# PowerSupply.net
KiCad netlist of a schematic drawn in Altium Designer
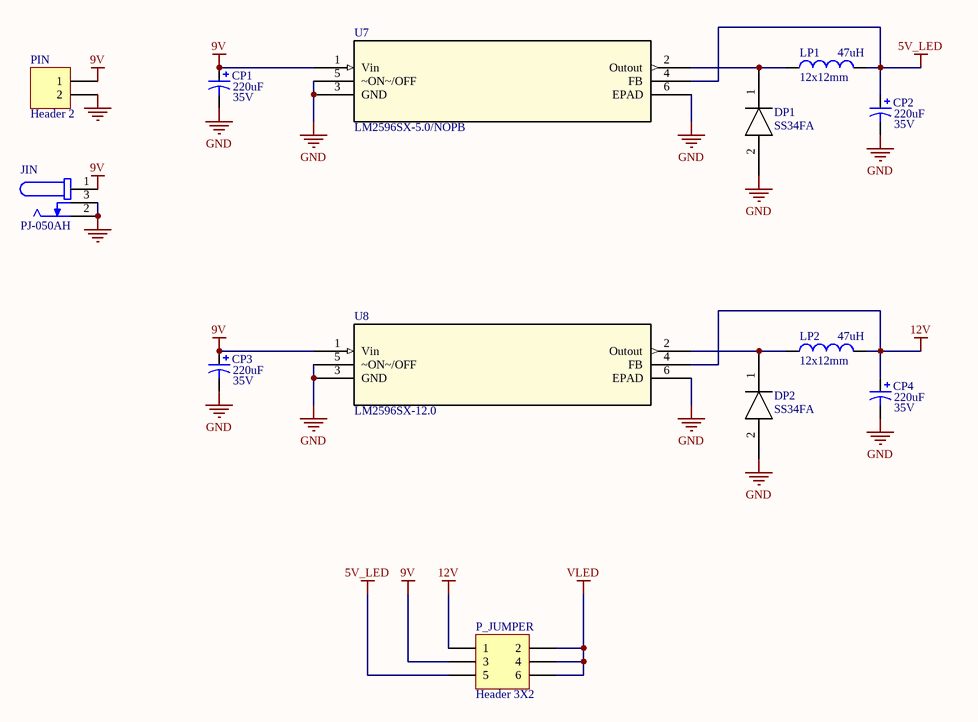
[diagram p0: PowerSupply.SchDoc]

(export (version "E")
  (design (tool "Eeschema 10.0.6"))
  (components
    (comp (ref "CP1")
      (value "220uF")
      (footprint "Cap10x10")
      (description "CAP ALUM 220UF 20% 35V SMD")
      (fields
        (field (name "TOLERANCE") "20%")
        (field (name "VOLTAGE") "35V")
        (field (name "Comment") "Cap Pol")
      )
      (libsource (lib "Miscellaneous Devices") (part "Cap Pol1"))
    )
    (comp (ref "CP2")
      (value "220uF")
      (footprint "Cap10x10")
      (description "CAP ALUM 220UF 20% 35V SMD")
      (fields
        (field (name "TOLERANCE") "20%")
        (field (name "VOLTAGE") "35V")
        (field (name "Comment") "Cap Pol")
      )
      (libsource (lib "Miscellaneous Devices") (part "Cap Pol1"))
    )
    (comp (ref "CP3")
      (value "220uF")
      (footprint "Cap10x10")
      (description "CAP ALUM 220UF 20% 35V SMD")
      (fields
        (field (name "TOLERANCE") "20%")
        (field (name "VOLTAGE") "35V")
        (field (name "Comment") "Cap Pol")
      )
      (libsource (lib "Miscellaneous Devices") (part "Cap Pol1"))
    )
    (comp (ref "CP4")
      (value "220uF")
      (footprint "Cap10x10")
      (description "CAP ALUM 220UF 20% 35V SMD")
      (fields
        (field (name "TOLERANCE") "20%")
        (field (name "VOLTAGE") "35V")
        (field (name "Comment") "Cap Pol")
      )
      (libsource (lib "Miscellaneous Devices") (part "Cap Pol1"))
    )
    (comp (ref "DP1")
      (value "SS34FA")
      (footprint "SOD_34FA_ONS")
      (description "DIODE SCHOTTKY 40V 3A SOD123FA")
      (fields (field (name "COPYRIGHT") "Copyright (C) 2018 Accelerated Designs. All rights reserved"))
      (libsource (lib "Symbols") (part "SS34FA"))
    )
    (comp (ref "DP2")
      (value "SS34FA")
      (footprint "SOD_34FA_ONS")
      (description "DIODE SCHOTTKY 40V 3A SOD123FA")
      (fields (field (name "COPYRIGHT") "Copyright (C) 2018 Accelerated Designs. All rights reserved"))
      (libsource (lib "Symbols") (part "SS34FA"))
    )
    (comp (ref "JIN")
      (value "PJ-050AH")
      (footprint "CUI_PJ-050AH")
      (description "2.0 x 6.0 mm, 5.0 A, Horizontal, Through Hole, Pick-n-Place Top, Dc Power Jack Connector")
      (fields (field (name "MF") "CUI Devices"))
      (libsource (lib "Schlib") (part "PJ-050AH"))
    )
    (comp (ref "LP1")
      (value "12x12mm")
      (footprint "12x12mmInductor")
      (description "FIXED IND 47UH 3.8A 60 MOHM SMD")
      (fields (field (name "ALTIUM_VALUE") "47uH") (field (name "TOLERANCE") "20%"))
      (libsource (lib "Miscellaneous Devices") (part "Inductor"))
    )
    (comp (ref "LP2")
      (value "12x12mm")
      (footprint "12x12mmInductor")
      (description "FIXED IND 47UH 3.8A 60 MOHM SMD")
      (fields (field (name "ALTIUM_VALUE") "47uH") (field (name "TOLERANCE") "20%"))
      (libsource (lib "Miscellaneous Devices") (part "Inductor"))
    )
    (comp (ref "PIN")
      (value "Header 2")
      (footprint "5.08mmScrew")
      (description "TERMINAL BLOCK, SCREW TYPE, 5.08")
      (fields (field (name "PUBLISHER") "Altium Limited"))
      (libsource (lib "Miscellaneous Connectors") (part "Header 2"))
    )
    (comp (ref "P_JUMPER")
      (value "Header 3X2")
      (footprint "HDR2X3")
      (description "CONN HEADER VERT 6POS 2.54MM")
      (fields (field (name "PUBLISHER") "Altium Limited"))
      (libsource (lib "Miscellaneous Connectors") (part "Header 3X2"))
    )
    (comp (ref "U7")
      (value "LM2596SX-5.0/NOPB")
      (footprint "TS5B")
      (fields (field (name "COPYRIGHT") "Copyright (C) 2018 Accelerated Designs. All rights reserved"))
      (libsource (lib "Schlib") (part "LM2596SX-5.0/NOP"))
    )
    (comp (ref "U8")
      (value "LM2596SX-12.0")
      (footprint "TS5B")
      (libsource (lib "Schlib") (part "LM2596SX-5.0/NOP"))
    )
  )
  (nets
    (net (code "1") (name "5V_LED") (class "Default")
      (node (ref "CP2") (pin "1") (pinfunction "1_1") (pintype "passive"))
      (node (ref "LP1") (pin "2") (pinfunction "2_2") (pintype "passive"))
      (node (ref "P_JUMPER") (pin "5") (pinfunction "5_5") (pintype "passive"))
      (node (ref "U7") (pin "4") (pinfunction "FB_4") (pintype "passive"))
    )
    (net (code "2") (name "9V") (class "Default")
      (node (ref "CP1") (pin "1") (pinfunction "1_1") (pintype "passive"))
      (node (ref "CP3") (pin "1") (pinfunction "1_1") (pintype "passive"))
      (node (ref "JIN") (pin "1") (pinfunction "1_1") (pintype "passive"))
      (node (ref "PIN") (pin "1") (pinfunction "1_1") (pintype "passive"))
      (node (ref "P_JUMPER") (pin "3") (pinfunction "3_3") (pintype "passive"))
      (node (ref "U7") (pin "1") (pinfunction "Vin_1") (pintype "input"))
      (node (ref "U8") (pin "1") (pinfunction "Vin_1") (pintype "input"))
    )
    (net (code "3") (name "12V") (class "Default")
      (node (ref "CP4") (pin "1") (pinfunction "1_1") (pintype "passive"))
      (node (ref "LP2") (pin "2") (pinfunction "2_2") (pintype "passive"))
      (node (ref "P_JUMPER") (pin "1") (pinfunction "1_1") (pintype "passive"))
      (node (ref "U8") (pin "4") (pinfunction "FB_4") (pintype "passive"))
    )
    (net (code "4") (name "GND") (class "Default")
      (node (ref "CP1") (pin "2") (pinfunction "2_2") (pintype "passive"))
      (node (ref "CP2") (pin "2") (pinfunction "2_2") (pintype "passive"))
      (node (ref "CP3") (pin "2") (pinfunction "2_2") (pintype "passive"))
      (node (ref "CP4") (pin "2") (pinfunction "2_2") (pintype "passive"))
      (node (ref "DP1") (pin "2") (pinfunction "2_2") (pintype "passive"))
      (node (ref "DP2") (pin "2") (pinfunction "2_2") (pintype "passive"))
      (node (ref "JIN") (pin "2") (pinfunction "2_2") (pintype "passive"))
      (node (ref "JIN") (pin "3") (pinfunction "3_3") (pintype "passive"))
      (node (ref "PIN") (pin "2") (pinfunction "2_2") (pintype "passive"))
      (node (ref "U7") (pin "3") (pinfunction "GND_3") (pintype "passive"))
      (node (ref "U7") (pin "5") (pinfunction "~ON~/OFF_5") (pintype "passive"))
      (node (ref "U7") (pin "6") (pinfunction "EPAD_6") (pintype "passive"))
      (node (ref "U8") (pin "3") (pinfunction "GND_3") (pintype "passive"))
      (node (ref "U8") (pin "5") (pinfunction "~ON~/OFF_5") (pintype "passive"))
      (node (ref "U8") (pin "6") (pinfunction "EPAD_6") (pintype "passive"))
    )
    (net (code "5") (name "Net-(U7-Outout)") (class "Default")
      (node (ref "DP1") (pin "1") (pinfunction "1_1") (pintype "passive"))
      (node (ref "LP1") (pin "1") (pinfunction "1_1") (pintype "passive"))
      (node (ref "U7") (pin "2") (pinfunction "Outout_2") (pintype "output"))
    )
    (net (code "6") (name "Net-(U8-Outout)") (class "Default")
      (node (ref "DP2") (pin "1") (pinfunction "1_1") (pintype "passive"))
      (node (ref "LP2") (pin "1") (pinfunction "1_1") (pintype "passive"))
      (node (ref "U8") (pin "2") (pinfunction "Outout_2") (pintype "output"))
    )
    (net (code "7") (name "VLED") (class "Default")
      (node (ref "P_JUMPER") (pin "2") (pinfunction "2_2") (pintype "passive"))
      (node (ref "P_JUMPER") (pin "4") (pinfunction "4_4") (pintype "passive"))
      (node (ref "P_JUMPER") (pin "6") (pinfunction "6_6") (pintype "passive"))
    )
  )
)
